# CM4_Conn.net
KiCad netlist of a schematic drawn in Altium Designer
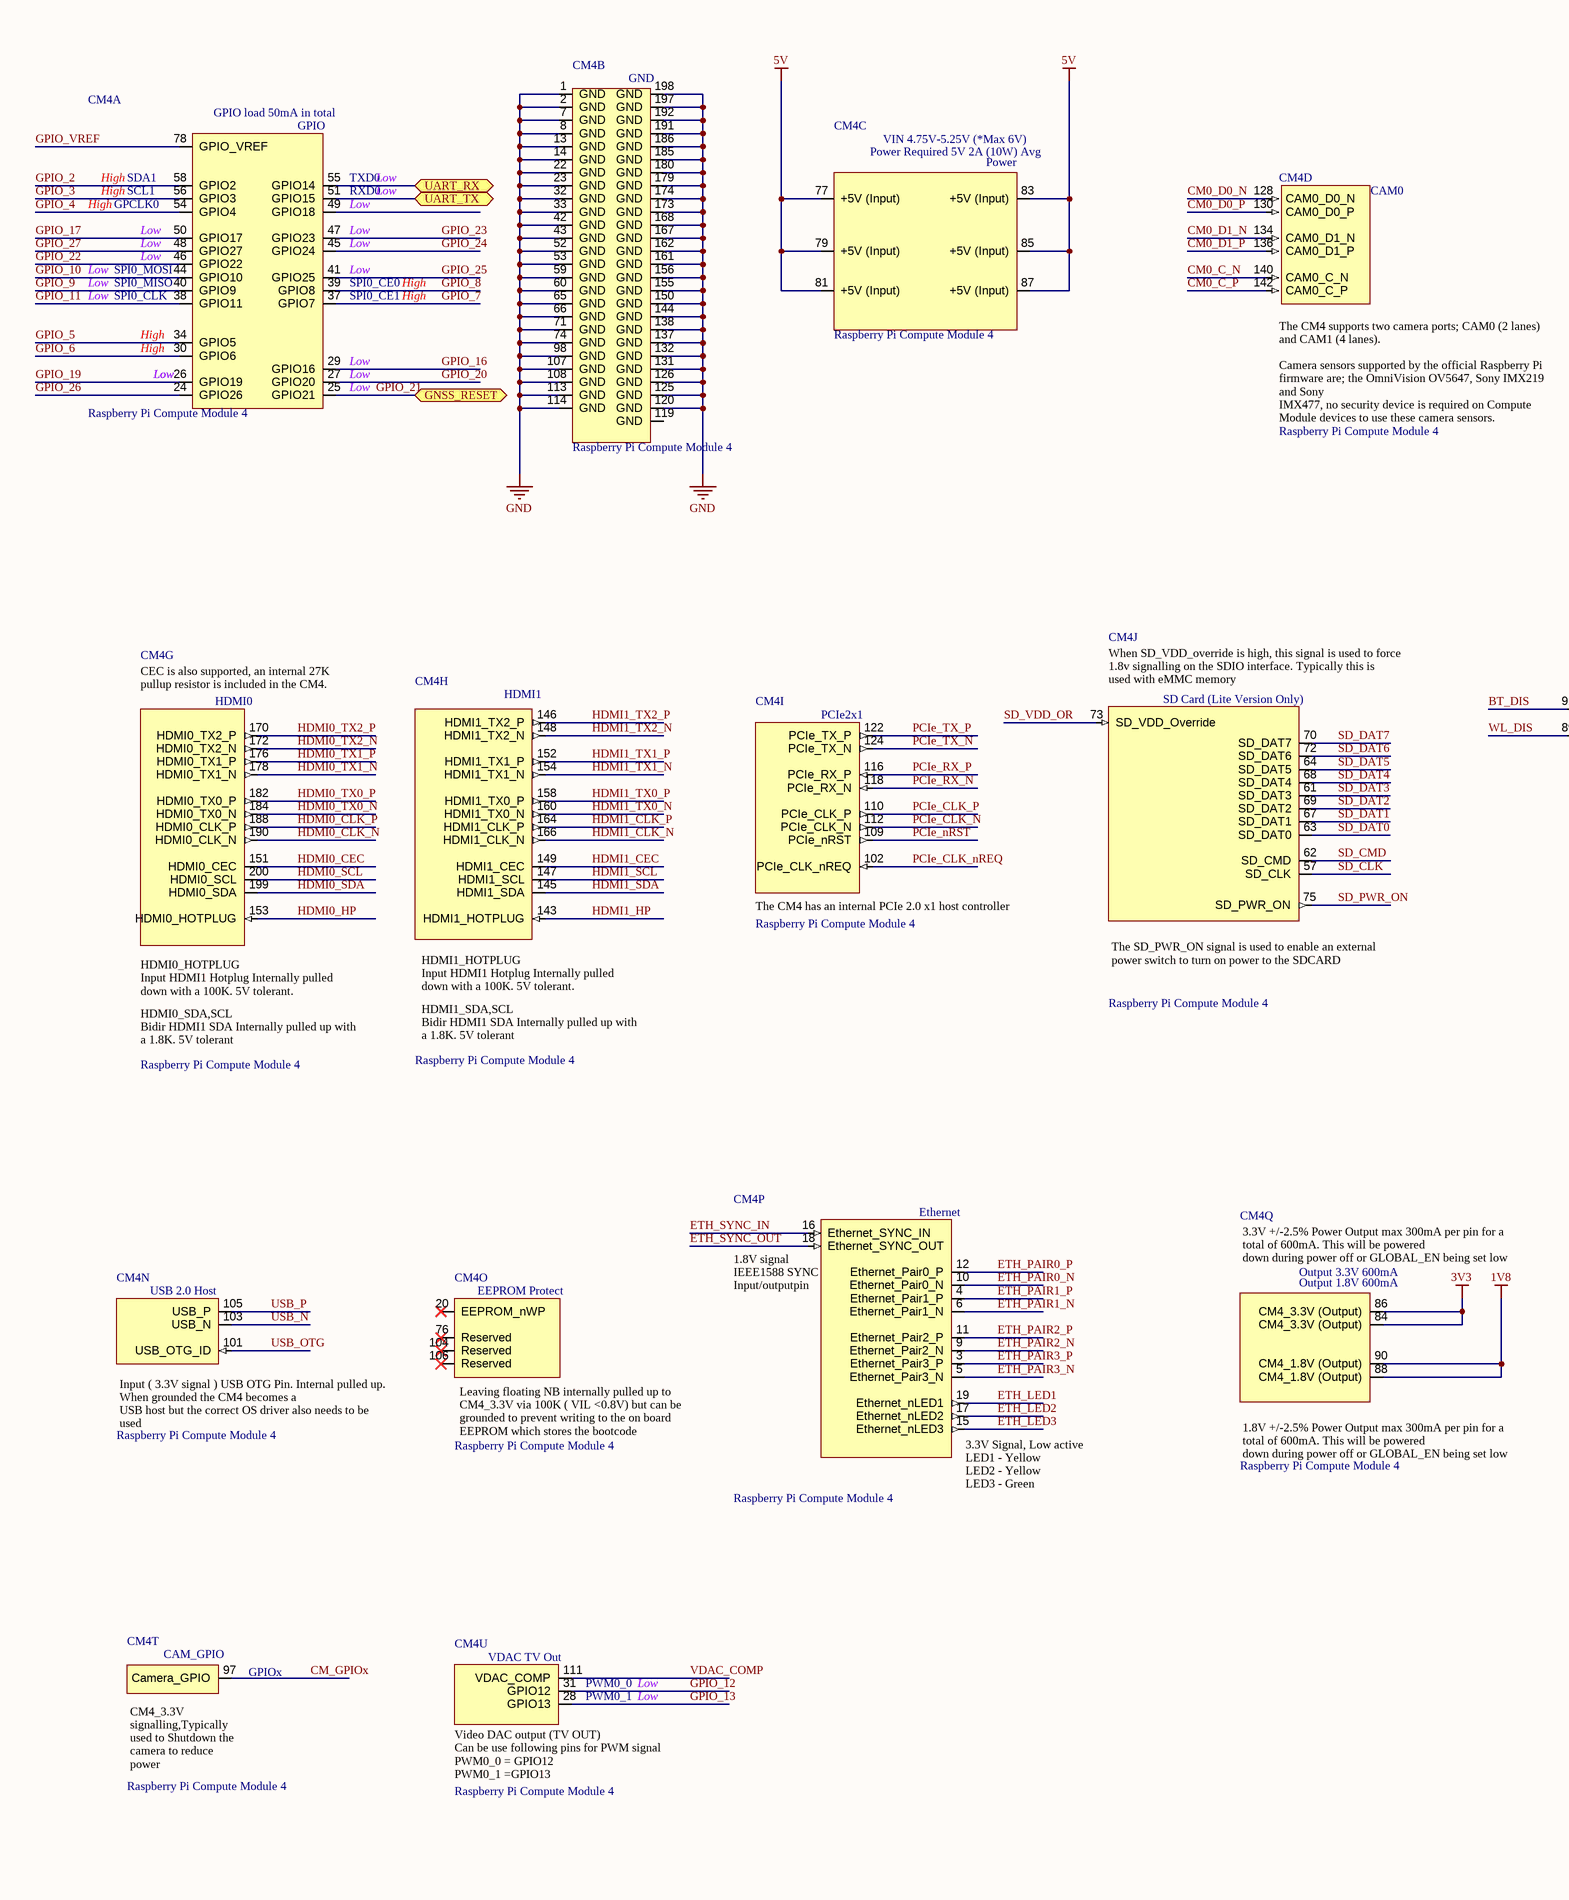
[diagram p0: CM4_Conn.SchDoc, left]
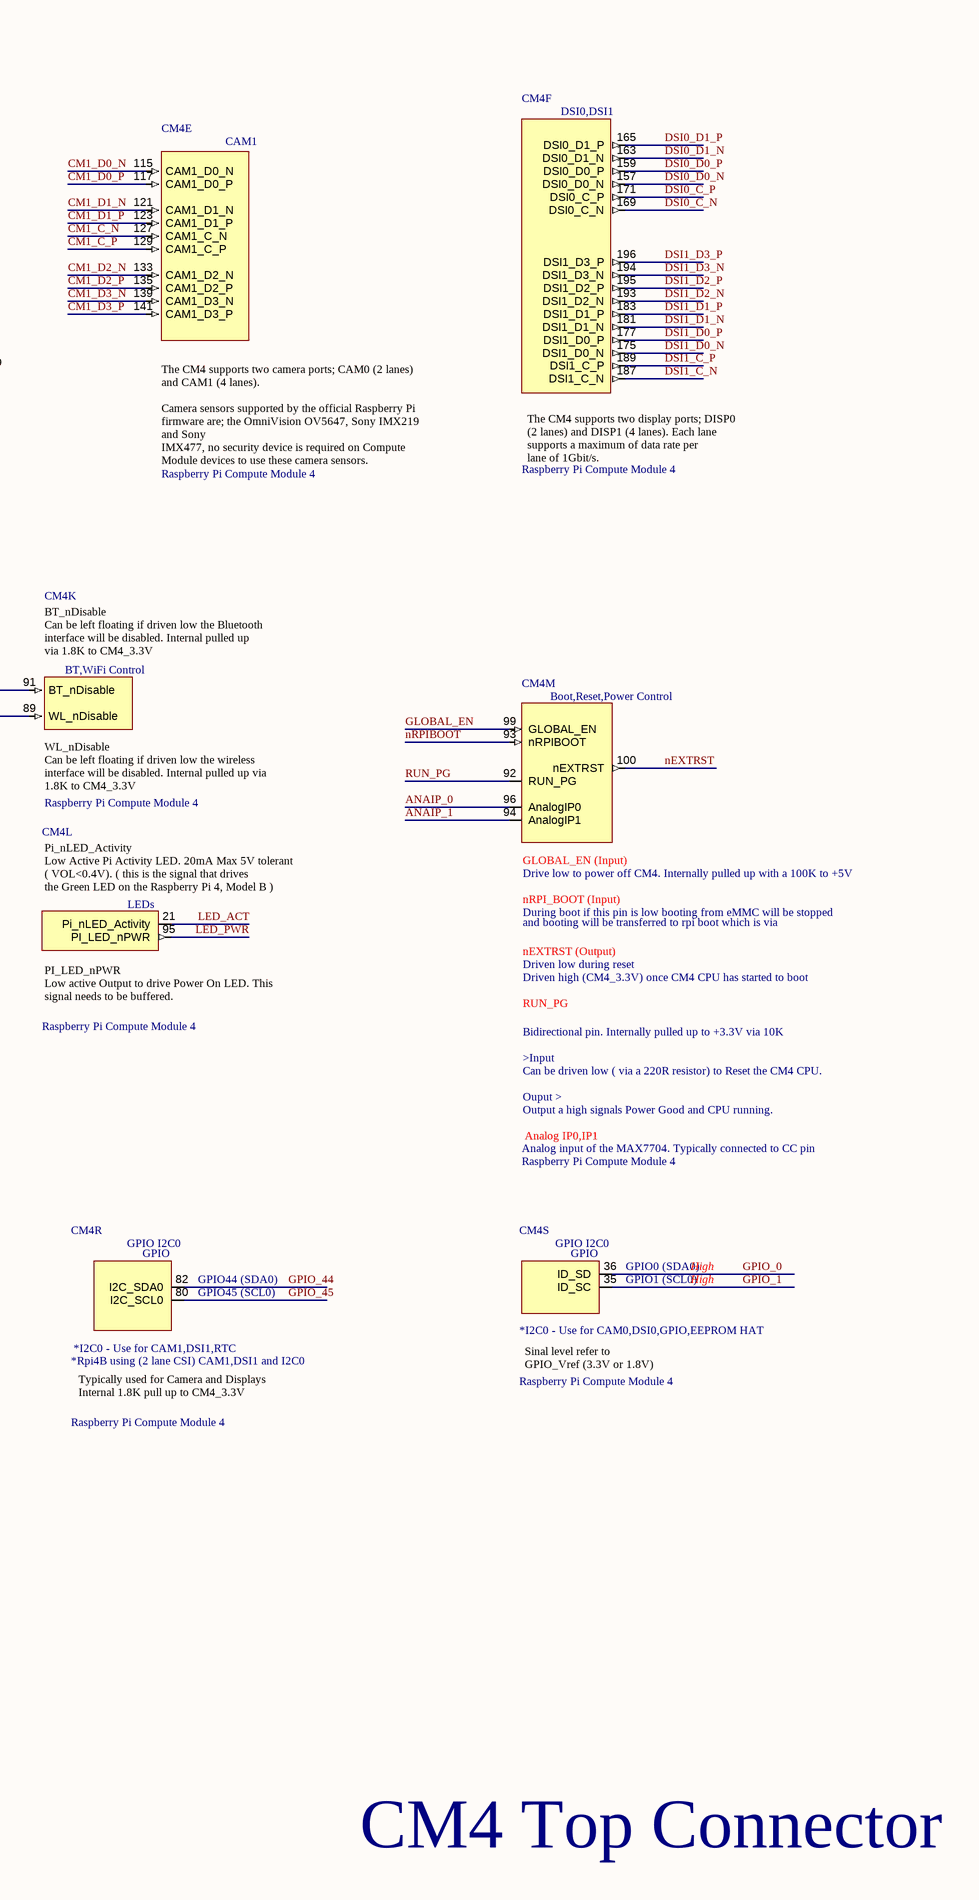
[diagram p1: CM4_Conn.SchDoc, right]

(export (version "E")
  (design (tool "Eeschema 10.0.6"))
  (components
    (comp (ref "CM4")
      (value "Raspberry Pi Compute Module 4")
      (footprint "CM4-F40C-100DS-0.4v_1.5mm_0mm")
      (description "Raspberry Pi Compute Module 4 by Amornthep Phunsin")
      (libsource (lib "CM4") (part "CM4"))
    )
  )
  (nets
    (net (code "1") (name "/ANAIP_0") (class "Default")
      (node (ref "CM4") (pin "96") (pinfunction "AnalogIP0_96") (pintype "passive"))
    )
    (net (code "2") (name "/ANAIP_1") (class "Default")
      (node (ref "CM4") (pin "94") (pinfunction "AnalogIP1_94") (pintype "passive"))
    )
    (net (code "3") (name "/BT_DIS") (class "Default")
      (node (ref "CM4") (pin "91") (pinfunction "BT_nDisable_91") (pintype "input"))
    )
    (net (code "4") (name "/CM0_C_N") (class "Default")
      (node (ref "CM4") (pin "140") (pinfunction "CAM0_C_N_140") (pintype "input"))
    )
    (net (code "5") (name "/CM0_C_P") (class "Default")
      (node (ref "CM4") (pin "142") (pinfunction "CAM0_C_P_142") (pintype "input"))
    )
    (net (code "6") (name "/CM0_D0_N") (class "Default")
      (node (ref "CM4") (pin "128") (pinfunction "CAM0_D0_N_128") (pintype "input"))
    )
    (net (code "7") (name "/CM0_D0_P") (class "Default")
      (node (ref "CM4") (pin "130") (pinfunction "CAM0_D0_P_130") (pintype "input"))
    )
    (net (code "8") (name "/CM0_D1_N") (class "Default")
      (node (ref "CM4") (pin "134") (pinfunction "CAM0_D1_N_134") (pintype "input"))
    )
    (net (code "9") (name "/CM0_D1_P") (class "Default")
      (node (ref "CM4") (pin "136") (pinfunction "CAM0_D1_P_136") (pintype "input"))
    )
    (net (code "10") (name "/CM1_C_N") (class "Default")
      (node (ref "CM4") (pin "127") (pinfunction "CAM1_C_N_127") (pintype "input"))
    )
    (net (code "11") (name "/CM1_C_P") (class "Default")
      (node (ref "CM4") (pin "129") (pinfunction "CAM1_C_P_129") (pintype "input"))
    )
    (net (code "12") (name "/CM1_D0_N") (class "Default")
      (node (ref "CM4") (pin "115") (pinfunction "CAM1_D0_N_115") (pintype "input"))
    )
    (net (code "13") (name "/CM1_D0_P") (class "Default")
      (node (ref "CM4") (pin "117") (pinfunction "CAM1_D0_P_117") (pintype "input"))
    )
    (net (code "14") (name "/CM1_D1_N") (class "Default")
      (node (ref "CM4") (pin "121") (pinfunction "CAM1_D1_N_121") (pintype "input"))
    )
    (net (code "15") (name "/CM1_D1_P") (class "Default")
      (node (ref "CM4") (pin "123") (pinfunction "CAM1_D1_P_123") (pintype "input"))
    )
    (net (code "16") (name "/CM1_D2_N") (class "Default")
      (node (ref "CM4") (pin "133") (pinfunction "CAM1_D2_N_133") (pintype "input"))
    )
    (net (code "17") (name "/CM1_D2_P") (class "Default")
      (node (ref "CM4") (pin "135") (pinfunction "CAM1_D2_P_135") (pintype "input"))
    )
    (net (code "18") (name "/CM1_D3_N") (class "Default")
      (node (ref "CM4") (pin "139") (pinfunction "CAM1_D3_N_139") (pintype "input"))
    )
    (net (code "19") (name "/CM1_D3_P") (class "Default")
      (node (ref "CM4") (pin "141") (pinfunction "CAM1_D3_P_141") (pintype "input"))
    )
    (net (code "20") (name "/CM_GPIOx") (class "Default")
      (node (ref "CM4") (pin "97") (pinfunction "Camera_GPIO_97") (pintype "passive"))
    )
    (net (code "21") (name "/DSI0_C_N") (class "Default")
      (node (ref "CM4") (pin "169") (pinfunction "DSI0_C_N_169") (pintype "output"))
    )
    (net (code "22") (name "/DSI0_C_P") (class "Default")
      (node (ref "CM4") (pin "171") (pinfunction "DSI0_C_P_171") (pintype "output"))
    )
    (net (code "23") (name "/DSI0_D0_N") (class "Default")
      (node (ref "CM4") (pin "157") (pinfunction "DSI0_D0_N_157") (pintype "output"))
    )
    (net (code "24") (name "/DSI0_D0_P") (class "Default")
      (node (ref "CM4") (pin "159") (pinfunction "DSI0_D0_P_159") (pintype "output"))
    )
    (net (code "25") (name "/DSI0_D1_N") (class "Default")
      (node (ref "CM4") (pin "163") (pinfunction "DSI0_D1_N_163") (pintype "output"))
    )
    (net (code "26") (name "/DSI0_D1_P") (class "Default")
      (node (ref "CM4") (pin "165") (pinfunction "DSI0_D1_P_165") (pintype "output"))
    )
    (net (code "27") (name "/DSI1_C_N") (class "Default")
      (node (ref "CM4") (pin "187") (pinfunction "DSI1_C_N_187") (pintype "output"))
    )
    (net (code "28") (name "/DSI1_C_P") (class "Default")
      (node (ref "CM4") (pin "189") (pinfunction "DSI1_C_P_189") (pintype "output"))
    )
    (net (code "29") (name "/DSI1_D0_N") (class "Default")
      (node (ref "CM4") (pin "175") (pinfunction "DSI1_D0_N_175") (pintype "output"))
    )
    (net (code "30") (name "/DSI1_D0_P") (class "Default")
      (node (ref "CM4") (pin "177") (pinfunction "DSI1_D0_P_177") (pintype "output"))
    )
    (net (code "31") (name "/DSI1_D1_N") (class "Default")
      (node (ref "CM4") (pin "181") (pinfunction "DSI1_D1_N_181") (pintype "output"))
    )
    (net (code "32") (name "/DSI1_D1_P") (class "Default")
      (node (ref "CM4") (pin "183") (pinfunction "DSI1_D1_P_183") (pintype "output"))
    )
    (net (code "33") (name "/DSI1_D2_N") (class "Default")
      (node (ref "CM4") (pin "193") (pinfunction "DSI1_D2_N_193") (pintype "output"))
    )
    (net (code "34") (name "/DSI1_D2_P") (class "Default")
      (node (ref "CM4") (pin "195") (pinfunction "DSI1_D2_P_195") (pintype "output"))
    )
    (net (code "35") (name "/DSI1_D3_N") (class "Default")
      (node (ref "CM4") (pin "194") (pinfunction "DSI1_D3_N_194") (pintype "output"))
    )
    (net (code "36") (name "/DSI1_D3_P") (class "Default")
      (node (ref "CM4") (pin "196") (pinfunction "DSI1_D3_P_196") (pintype "output"))
    )
    (net (code "37") (name "/ETH_LED1") (class "Default")
      (node (ref "CM4") (pin "19") (pinfunction "Ethernet_nLED1_19") (pintype "output"))
    )
    (net (code "38") (name "/ETH_LED2") (class "Default")
      (node (ref "CM4") (pin "17") (pinfunction "Ethernet_nLED2_17") (pintype "output"))
    )
    (net (code "39") (name "/ETH_LED3") (class "Default")
      (node (ref "CM4") (pin "15") (pinfunction "Ethernet_nLED3_15") (pintype "output"))
    )
    (net (code "40") (name "/ETH_PAIR0_N") (class "Default")
      (node (ref "CM4") (pin "10") (pinfunction "Ethernet_Pair0_N_10") (pintype "passive"))
    )
    (net (code "41") (name "/ETH_PAIR0_P") (class "Default")
      (node (ref "CM4") (pin "12") (pinfunction "Ethernet_Pair0_P_12") (pintype "passive"))
    )
    (net (code "42") (name "/ETH_PAIR1_N") (class "Default")
      (node (ref "CM4") (pin "6") (pinfunction "Ethernet_Pair1_N_6") (pintype "passive"))
    )
    (net (code "43") (name "/ETH_PAIR1_P") (class "Default")
      (node (ref "CM4") (pin "4") (pinfunction "Ethernet_Pair1_P_4") (pintype "passive"))
    )
    (net (code "44") (name "/ETH_PAIR2_N") (class "Default")
      (node (ref "CM4") (pin "9") (pinfunction "Ethernet_Pair2_N_9") (pintype "passive"))
    )
    (net (code "45") (name "/ETH_PAIR2_P") (class "Default")
      (node (ref "CM4") (pin "11") (pinfunction "Ethernet_Pair2_P_11") (pintype "passive"))
    )
    (net (code "46") (name "/ETH_PAIR3_N") (class "Default")
      (node (ref "CM4") (pin "5") (pinfunction "Ethernet_Pair3_N_5") (pintype "passive"))
    )
    (net (code "47") (name "/ETH_PAIR3_P") (class "Default")
      (node (ref "CM4") (pin "3") (pinfunction "Ethernet_Pair3_P_3") (pintype "passive"))
    )
    (net (code "48") (name "/ETH_SYNC_IN") (class "Default")
      (node (ref "CM4") (pin "16") (pinfunction "Ethernet_SYNC_IN_16") (pintype "input"))
    )
    (net (code "49") (name "/ETH_SYNC_OUT") (class "Default")
      (node (ref "CM4") (pin "18") (pinfunction "Ethernet_SYNC_OUT_18") (pintype "input"))
    )
    (net (code "50") (name "/GLOBAL_EN") (class "Default")
      (node (ref "CM4") (pin "99") (pinfunction "GLOBAL_EN_99") (pintype "input"))
    )
    (net (code "51") (name "/GPIO_0") (class "Default")
      (node (ref "CM4") (pin "36") (pinfunction "ID_SD_36") (pintype "passive"))
    )
    (net (code "52") (name "/GPIO_1") (class "Default")
      (node (ref "CM4") (pin "35") (pinfunction "ID_SC_35") (pintype "passive"))
    )
    (net (code "53") (name "/GPIO_2") (class "Default")
      (node (ref "CM4") (pin "58") (pinfunction "GPIO2_58") (pintype "passive"))
    )
    (net (code "54") (name "/GPIO_3") (class "Default")
      (node (ref "CM4") (pin "56") (pinfunction "GPIO3_56") (pintype "passive"))
    )
    (net (code "55") (name "/GPIO_4") (class "Default")
      (node (ref "CM4") (pin "54") (pinfunction "GPIO4_54") (pintype "passive"))
    )
    (net (code "56") (name "/GPIO_5") (class "Default")
      (node (ref "CM4") (pin "34") (pinfunction "GPIO5_34") (pintype "passive"))
    )
    (net (code "57") (name "/GPIO_6") (class "Default")
      (node (ref "CM4") (pin "30") (pinfunction "GPIO6_30") (pintype "passive"))
    )
    (net (code "58") (name "/GPIO_7") (class "Default")
      (node (ref "CM4") (pin "37") (pinfunction "GPIO7_37") (pintype "passive"))
    )
    (net (code "59") (name "/GPIO_8") (class "Default")
      (node (ref "CM4") (pin "39") (pinfunction "GPIO8_39") (pintype "passive"))
    )
    (net (code "60") (name "/GPIO_9") (class "Default")
      (node (ref "CM4") (pin "40") (pinfunction "GPIO9_40") (pintype "passive"))
    )
    (net (code "61") (name "/GPIO_10") (class "Default")
      (node (ref "CM4") (pin "44") (pinfunction "GPIO10_44") (pintype "passive"))
    )
    (net (code "62") (name "/GPIO_11") (class "Default")
      (node (ref "CM4") (pin "38") (pinfunction "GPIO11_38") (pintype "passive"))
    )
    (net (code "63") (name "/GPIO_12") (class "Default")
      (node (ref "CM4") (pin "31") (pinfunction "GPIO12_31") (pintype "passive"))
    )
    (net (code "64") (name "/GPIO_13") (class "Default")
      (node (ref "CM4") (pin "28") (pinfunction "GPIO13_28") (pintype "passive"))
    )
    (net (code "65") (name "/GPIO_16") (class "Default")
      (node (ref "CM4") (pin "29") (pinfunction "GPIO16_29") (pintype "passive"))
    )
    (net (code "66") (name "/GPIO_17") (class "Default")
      (node (ref "CM4") (pin "50") (pinfunction "GPIO17_50") (pintype "passive"))
    )
    (net (code "67") (name "/GPIO_19") (class "Default")
      (node (ref "CM4") (pin "26") (pinfunction "GPIO19_26") (pintype "passive"))
    )
    (net (code "68") (name "/GPIO_20") (class "Default")
      (node (ref "CM4") (pin "27") (pinfunction "GPIO20_27") (pintype "passive"))
    )
    (net (code "69") (name "/GPIO_21") (class "Default")
      (node (ref "CM4") (pin "25") (pinfunction "GPIO21_25") (pintype "passive"))
    )
    (net (code "70") (name "/GPIO_22") (class "Default")
      (node (ref "CM4") (pin "46") (pinfunction "GPIO22_46") (pintype "passive"))
    )
    (net (code "71") (name "/GPIO_23") (class "Default")
      (node (ref "CM4") (pin "47") (pinfunction "GPIO23_47") (pintype "passive"))
    )
    (net (code "72") (name "/GPIO_24") (class "Default")
      (node (ref "CM4") (pin "45") (pinfunction "GPIO24_45") (pintype "passive"))
    )
    (net (code "73") (name "/GPIO_25") (class "Default")
      (node (ref "CM4") (pin "41") (pinfunction "GPIO25_41") (pintype "passive"))
    )
    (net (code "74") (name "/GPIO_26") (class "Default")
      (node (ref "CM4") (pin "24") (pinfunction "GPIO26_24") (pintype "passive"))
    )
    (net (code "75") (name "/GPIO_27") (class "Default")
      (node (ref "CM4") (pin "48") (pinfunction "GPIO27_48") (pintype "passive"))
    )
    (net (code "76") (name "/GPIO_44") (class "Default")
      (node (ref "CM4") (pin "82") (pinfunction "I2C_SDA0_82") (pintype "passive"))
    )
    (net (code "77") (name "/GPIO_45") (class "Default")
      (node (ref "CM4") (pin "80") (pinfunction "I2C_SCL0_80") (pintype "passive"))
    )
    (net (code "78") (name "/GPIO_VREF") (class "Default")
      (node (ref "CM4") (pin "78") (pinfunction "GPIO_VREF_78") (pintype "power_in"))
    )
    (net (code "79") (name "/HDMI0_CEC") (class "Default")
      (node (ref "CM4") (pin "151") (pinfunction "HDMI0_CEC_151") (pintype "open_collector"))
    )
    (net (code "80") (name "/HDMI0_CLK_N") (class "Default")
      (node (ref "CM4") (pin "190") (pinfunction "HDMI0_CLK_N_190") (pintype "output"))
    )
    (net (code "81") (name "/HDMI0_CLK_P") (class "Default")
      (node (ref "CM4") (pin "188") (pinfunction "HDMI0_CLK_P_188") (pintype "output"))
    )
    (net (code "82") (name "/HDMI0_HP") (class "Default")
      (node (ref "CM4") (pin "153") (pinfunction "HDMI0_HOTPLUG_153") (pintype "input"))
    )
    (net (code "83") (name "/HDMI0_SCL") (class "Default")
      (node (ref "CM4") (pin "200") (pinfunction "HDMI0_SCL_200") (pintype "open_collector"))
    )
    (net (code "84") (name "/HDMI0_SDA") (class "Default")
      (node (ref "CM4") (pin "199") (pinfunction "HDMI0_SDA_199") (pintype "bidirectional"))
    )
    (net (code "85") (name "/HDMI0_TX0_N") (class "Default")
      (node (ref "CM4") (pin "184") (pinfunction "HDMI0_TX0_N_184") (pintype "output"))
    )
    (net (code "86") (name "/HDMI0_TX0_P") (class "Default")
      (node (ref "CM4") (pin "182") (pinfunction "HDMI0_TX0_P_182") (pintype "output"))
    )
    (net (code "87") (name "/HDMI0_TX1_N") (class "Default")
      (node (ref "CM4") (pin "178") (pinfunction "HDMI0_TX1_N_178") (pintype "output"))
    )
    (net (code "88") (name "/HDMI0_TX1_P") (class "Default")
      (node (ref "CM4") (pin "176") (pinfunction "HDMI0_TX1_P_176") (pintype "output"))
    )
    (net (code "89") (name "/HDMI0_TX2_N") (class "Default")
      (node (ref "CM4") (pin "172") (pinfunction "HDMI0_TX2_N_172") (pintype "output"))
    )
    (net (code "90") (name "/HDMI0_TX2_P") (class "Default")
      (node (ref "CM4") (pin "170") (pinfunction "HDMI0_TX2_P_170") (pintype "output"))
    )
    (net (code "91") (name "/HDMI1_CEC") (class "Default")
      (node (ref "CM4") (pin "149") (pinfunction "HDMI1_CEC_149") (pintype "open_collector"))
    )
    (net (code "92") (name "/HDMI1_CLK_N") (class "Default")
      (node (ref "CM4") (pin "166") (pinfunction "HDMI1_CLK_N_166") (pintype "output"))
    )
    (net (code "93") (name "/HDMI1_CLK_P") (class "Default")
      (node (ref "CM4") (pin "164") (pinfunction "HDMI1_CLK_P_164") (pintype "output"))
    )
    (net (code "94") (name "/HDMI1_HP") (class "Default")
      (node (ref "CM4") (pin "143") (pinfunction "HDMI1_HOTPLUG_143") (pintype "input"))
    )
    (net (code "95") (name "/HDMI1_SCL") (class "Default")
      (node (ref "CM4") (pin "147") (pinfunction "HDMI1_SCL_147") (pintype "open_collector"))
    )
    (net (code "96") (name "/HDMI1_SDA") (class "Default")
      (node (ref "CM4") (pin "145") (pinfunction "HDMI1_SDA_145") (pintype "bidirectional"))
    )
    (net (code "97") (name "/HDMI1_TX0_N") (class "Default")
      (node (ref "CM4") (pin "160") (pinfunction "HDMI1_TX0_N_160") (pintype "output"))
    )
    (net (code "98") (name "/HDMI1_TX0_P") (class "Default")
      (node (ref "CM4") (pin "158") (pinfunction "HDMI1_TX0_P_158") (pintype "output"))
    )
    (net (code "99") (name "/HDMI1_TX1_N") (class "Default")
      (node (ref "CM4") (pin "154") (pinfunction "HDMI1_TX1_N_154") (pintype "output"))
    )
    (net (code "100") (name "/HDMI1_TX1_P") (class "Default")
      (node (ref "CM4") (pin "152") (pinfunction "HDMI1_TX1_P_152") (pintype "output"))
    )
    (net (code "101") (name "/HDMI1_TX2_N") (class "Default")
      (node (ref "CM4") (pin "148") (pinfunction "HDMI1_TX2_N_148") (pintype "output"))
    )
    (net (code "102") (name "/HDMI1_TX2_P") (class "Default")
      (node (ref "CM4") (pin "146") (pinfunction "HDMI1_TX2_P_146") (pintype "output"))
    )
    (net (code "103") (name "/LED_ACT") (class "Default")
      (node (ref "CM4") (pin "21") (pinfunction "Pi_nLED_Activity_21") (pintype "open_collector"))
    )
    (net (code "104") (name "/LED_PWR") (class "Default")
      (node (ref "CM4") (pin "95") (pinfunction "PI_LED_nPWR_95") (pintype "output"))
    )
    (net (code "105") (name "/PCIe_CLK_N") (class "Default")
      (node (ref "CM4") (pin "112") (pinfunction "PCIe_CLK_N_112") (pintype "output"))
    )
    (net (code "106") (name "/PCIe_CLK_P") (class "Default")
      (node (ref "CM4") (pin "110") (pinfunction "PCIe_CLK_P_110") (pintype "output"))
    )
    (net (code "107") (name "/PCIe_CLK_nREQ") (class "Default")
      (node (ref "CM4") (pin "102") (pinfunction "PCIe_CLK_nREQ_102") (pintype "input"))
    )
    (net (code "108") (name "/PCIe_RX_N") (class "Default")
      (node (ref "CM4") (pin "118") (pinfunction "PCIe_RX_N_118") (pintype "input"))
    )
    (net (code "109") (name "/PCIe_RX_P") (class "Default")
      (node (ref "CM4") (pin "116") (pinfunction "PCIe_RX_P_116") (pintype "input"))
    )
    (net (code "110") (name "/PCIe_TX_N") (class "Default")
      (node (ref "CM4") (pin "124") (pinfunction "PCIe_TX_N_124") (pintype "output"))
    )
    (net (code "111") (name "/PCIe_TX_P") (class "Default")
      (node (ref "CM4") (pin "122") (pinfunction "PCIe_TX_P_122") (pintype "output"))
    )
    (net (code "112") (name "/PCIe_nRST") (class "Default")
      (node (ref "CM4") (pin "109") (pinfunction "PCIe_nRST_109") (pintype "output"))
    )
    (net (code "113") (name "/RUN_PG") (class "Default")
      (node (ref "CM4") (pin "92") (pinfunction "RUN_PG_92") (pintype "passive"))
    )
    (net (code "114") (name "/SD_CLK") (class "Default")
      (node (ref "CM4") (pin "57") (pinfunction "SD_CLK_57") (pintype "passive"))
    )
    (net (code "115") (name "/SD_CMD") (class "Default")
      (node (ref "CM4") (pin "62") (pinfunction "SD_CMD_62") (pintype "passive"))
    )
    (net (code "116") (name "/SD_DAT0") (class "Default")
      (node (ref "CM4") (pin "63") (pinfunction "SD_DAT0_63") (pintype "passive"))
    )
    (net (code "117") (name "/SD_DAT1") (class "Default")
      (node (ref "CM4") (pin "67") (pinfunction "SD_DAT1_67") (pintype "passive"))
    )
    (net (code "118") (name "/SD_DAT2") (class "Default")
      (node (ref "CM4") (pin "69") (pinfunction "SD_DAT2_69") (pintype "passive"))
    )
    (net (code "119") (name "/SD_DAT3") (class "Default")
      (node (ref "CM4") (pin "61") (pinfunction "SD_DAT3_61") (pintype "passive"))
    )
    (net (code "120") (name "/SD_DAT4") (class "Default")
      (node (ref "CM4") (pin "68") (pinfunction "SD_DAT4_68") (pintype "passive"))
    )
    (net (code "121") (name "/SD_DAT5") (class "Default")
      (node (ref "CM4") (pin "64") (pinfunction "SD_DAT5_64") (pintype "passive"))
    )
    (net (code "122") (name "/SD_DAT6") (class "Default")
      (node (ref "CM4") (pin "72") (pinfunction "SD_DAT6_72") (pintype "passive"))
    )
    (net (code "123") (name "/SD_DAT7") (class "Default")
      (node (ref "CM4") (pin "70") (pinfunction "SD_DAT7_70") (pintype "passive"))
    )
    (net (code "124") (name "/SD_PWR_ON") (class "Default")
      (node (ref "CM4") (pin "75") (pinfunction "SD_PWR_ON_75") (pintype "output"))
    )
    (net (code "125") (name "/SD_VDD_OR") (class "Default")
      (node (ref "CM4") (pin "73") (pinfunction "SD_VDD_Override_73") (pintype "input"))
    )
    (net (code "126") (name "/UART_RX") (class "Default")
      (node (ref "CM4") (pin "55") (pinfunction "GPIO14_55") (pintype "passive"))
    )
    (net (code "127") (name "/UART_TX") (class "Default")
      (node (ref "CM4") (pin "51") (pinfunction "GPIO15_51") (pintype "passive"))
    )
    (net (code "128") (name "/USB_N") (class "Default")
      (node (ref "CM4") (pin "103") (pinfunction "USB_N_103") (pintype "passive"))
    )
    (net (code "129") (name "/USB_OTG") (class "Default")
      (node (ref "CM4") (pin "101") (pinfunction "USB_OTG_ID_101") (pintype "input"))
    )
    (net (code "130") (name "/USB_P") (class "Default")
      (node (ref "CM4") (pin "105") (pinfunction "USB_P_105") (pintype "passive"))
    )
    (net (code "131") (name "/VDAC_COMP") (class "Default")
      (node (ref "CM4") (pin "111") (pinfunction "VDAC_COMP_111") (pintype "passive"))
    )
    (net (code "132") (name "/WL_DIS") (class "Default")
      (node (ref "CM4") (pin "89") (pinfunction "WL_nDisable_89") (pintype "input"))
    )
    (net (code "133") (name "/nEXTRST") (class "Default")
      (node (ref "CM4") (pin "100") (pinfunction "nEXTRST_100") (pintype "output"))
    )
    (net (code "134") (name "/nRPIBOOT") (class "Default")
      (node (ref "CM4") (pin "93") (pinfunction "nRPIBOOT_93") (pintype "input"))
    )
    (net (code "135") (name "1V8") (class "Default")
      (node (ref "CM4") (pin "88") (pinfunction "CM4_1.8V_(Output)_88") (pintype "power_in"))
      (node (ref "CM4") (pin "90") (pinfunction "CM4_1.8V_(Output)_90") (pintype "power_in"))
    )
    (net (code "136") (name "3V3") (class "Default")
      (node (ref "CM4") (pin "84") (pinfunction "CM4_3.3V_(Output)_84") (pintype "power_in"))
      (node (ref "CM4") (pin "86") (pinfunction "CM4_3.3V_(Output)_86") (pintype "power_in"))
    )
    (net (code "137") (name "5V") (class "Default")
      (node (ref "CM4") (pin "77") (pinfunction "+5V_(Input)_77") (pintype "power_in"))
      (node (ref "CM4") (pin "79") (pinfunction "+5V_(Input)_79") (pintype "power_in"))
      (node (ref "CM4") (pin "81") (pinfunction "+5V_(Input)_81") (pintype "power_in"))
      (node (ref "CM4") (pin "83") (pinfunction "+5V_(Input)_83") (pintype "power_in"))
      (node (ref "CM4") (pin "85") (pinfunction "+5V_(Input)_85") (pintype "power_in"))
      (node (ref "CM4") (pin "87") (pinfunction "+5V_(Input)_87") (pintype "power_in"))
    )
    (net (code "138") (name "GND") (class "Default")
      (node (ref "CM4") (pin "1") (pinfunction "GND_1") (pintype "power_in"))
      (node (ref "CM4") (pin "107") (pinfunction "GND_107") (pintype "power_in"))
      (node (ref "CM4") (pin "108") (pinfunction "GND_108") (pintype "power_in"))
      (node (ref "CM4") (pin "113") (pinfunction "GND_113") (pintype "power_in"))
      (node (ref "CM4") (pin "114") (pinfunction "GND_114") (pintype "power_in"))
      (node (ref "CM4") (pin "120") (pinfunction "GND_120") (pintype "power_in"))
      (node (ref "CM4") (pin "125") (pinfunction "GND_125") (pintype "power_in"))
      (node (ref "CM4") (pin "126") (pinfunction "GND_126") (pintype "power_in"))
      (node (ref "CM4") (pin "13") (pinfunction "GND_13") (pintype "power_in"))
      (node (ref "CM4") (pin "131") (pinfunction "GND_131") (pintype "power_in"))
      (node (ref "CM4") (pin "132") (pinfunction "GND_132") (pintype "power_in"))
      (node (ref "CM4") (pin "137") (pinfunction "GND_137") (pintype "power_in"))
      (node (ref "CM4") (pin "138") (pinfunction "GND_138") (pintype "power_in"))
      (node (ref "CM4") (pin "14") (pinfunction "GND_14") (pintype "power_in"))
      (node (ref "CM4") (pin "144") (pinfunction "GND_144") (pintype "power_in"))
      (node (ref "CM4") (pin "150") (pinfunction "GND_150") (pintype "power_in"))
      (node (ref "CM4") (pin "155") (pinfunction "GND_155") (pintype "power_in"))
      (node (ref "CM4") (pin "156") (pinfunction "GND_156") (pintype "power_in"))
      (node (ref "CM4") (pin "161") (pinfunction "GND_161") (pintype "power_in"))
      (node (ref "CM4") (pin "162") (pinfunction "GND_162") (pintype "power_in"))
      (node (ref "CM4") (pin "167") (pinfunction "GND_167") (pintype "power_in"))
      (node (ref "CM4") (pin "168") (pinfunction "GND_168") (pintype "power_in"))
      (node (ref "CM4") (pin "173") (pinfunction "GND_173") (pintype "power_in"))
      (node (ref "CM4") (pin "174") (pinfunction "GND_174") (pintype "power_in"))
      (node (ref "CM4") (pin "179") (pinfunction "GND_179") (pintype "power_in"))
      (node (ref "CM4") (pin "180") (pinfunction "GND_180") (pintype "power_in"))
      (node (ref "CM4") (pin "185") (pinfunction "GND_185") (pintype "power_in"))
      (node (ref "CM4") (pin "186") (pinfunction "GND_186") (pintype "power_in"))
      (node (ref "CM4") (pin "191") (pinfunction "GND_191") (pintype "power_in"))
      (node (ref "CM4") (pin "192") (pinfunction "GND_192") (pintype "power_in"))
      (node (ref "CM4") (pin "197") (pinfunction "GND_197") (pintype "power_in"))
      (node (ref "CM4") (pin "198") (pinfunction "GND_198") (pintype "power_in"))
      (node (ref "CM4") (pin "2") (pinfunction "GND_2") (pintype "power_in"))
      (node (ref "CM4") (pin "22") (pinfunction "GND_22") (pintype "power_in"))
      (node (ref "CM4") (pin "23") (pinfunction "GND_23") (pintype "power_in"))
      (node (ref "CM4") (pin "32") (pinfunction "GND_32") (pintype "power_in"))
      (node (ref "CM4") (pin "33") (pinfunction "GND_33") (pintype "power_in"))
      (node (ref "CM4") (pin "42") (pinfunction "GND_42") (pintype "power_in"))
      (node (ref "CM4") (pin "43") (pinfunction "GND_43") (pintype "power_in"))
      (node (ref "CM4") (pin "52") (pinfunction "GND_52") (pintype "power_in"))
      (node (ref "CM4") (pin "53") (pinfunction "GND_53") (pintype "power_in"))
      (node (ref "CM4") (pin "59") (pinfunction "GND_59") (pintype "power_in"))
      (node (ref "CM4") (pin "60") (pinfunction "GND_60") (pintype "power_in"))
      (node (ref "CM4") (pin "65") (pinfunction "GND_65") (pintype "power_in"))
      (node (ref "CM4") (pin "66") (pinfunction "GND_66") (pintype "power_in"))
      (node (ref "CM4") (pin "7") (pinfunction "GND_7") (pintype "power_in"))
      (node (ref "CM4") (pin "71") (pinfunction "GND_71") (pintype "power_in"))
      (node (ref "CM4") (pin "74") (pinfunction "GND_74") (pintype "power_in"))
      (node (ref "CM4") (pin "8") (pinfunction "GND_8") (pintype "power_in"))
      (node (ref "CM4") (pin "98") (pinfunction "GND_98") (pintype "power_in"))
    )
    (net (code "139") (name "unconnected-(CM4A-GPIO18-Pad49)") (class "Default")
      (node (ref "CM4") (pin "49") (pinfunction "GPIO18_49") (pintype "passive"))
    )
    (net (code "140") (name "unconnected-(CM4B-GND-Pad119)") (class "Default")
      (node (ref "CM4") (pin "119") (pinfunction "GND_119") (pintype "power_in"))
    )
    (net (code "141") (name "unconnected-(CM4O-EEPROM_nWP-Pad20)") (class "Default")
      (node (ref "CM4") (pin "20") (pinfunction "EEPROM_nWP_20") (pintype "passive+no_connect"))
    )
    (net (code "142") (name "unconnected-(CM4O-Reserved-Pad76)") (class "Default")
      (node (ref "CM4") (pin "76") (pinfunction "Reserved_76") (pintype "passive+no_connect"))
    )
    (net (code "143") (name "unconnected-(CM4O-Reserved-Pad104)") (class "Default")
      (node (ref "CM4") (pin "104") (pinfunction "Reserved_104") (pintype "passive+no_connect"))
    )
    (net (code "144") (name "unconnected-(CM4O-Reserved-Pad106)") (class "Default")
      (node (ref "CM4") (pin "106") (pinfunction "Reserved_106") (pintype "passive+no_connect"))
    )
  )
)
